# adc.net
KiCad netlist of a schematic drawn in EAGLE
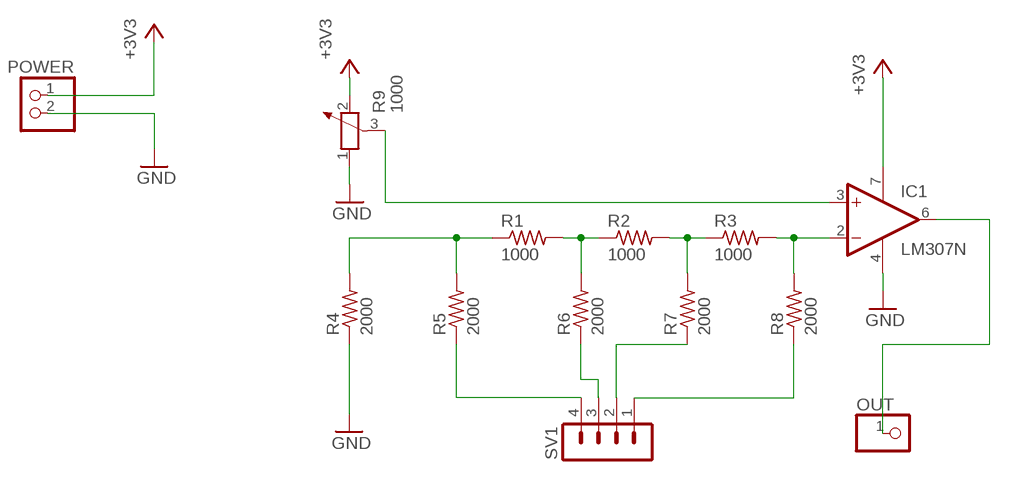
[diagram p0: schematic, sheet 1]

(export (version "E")
  (design (tool "Eeschema 10.0.6"))
  (components
    (comp (ref "IC1")
      (value "LM307N")
      (footprint "eagle-import:DIL08")
      (libsource (lib "eagle-import") (part "LM307N"))
    )
    (comp (ref "OUT")
      (value "PINHD-1X1")
      (footprint "eagle-import:1X01")
      (libsource (lib "eagle-import") (part "PINHD-1X1"))
    )
    (comp (ref "POWER")
      (value "PINHD-1X2")
      (footprint "eagle-import:1X02")
      (libsource (lib "eagle-import") (part "PINHD-1X2"))
    )
    (comp (ref "R1")
      (value "1000")
      (footprint "eagle-import:0204_7")
      (libsource (lib "eagle-import") (part "R-US_0204/7"))
    )
    (comp (ref "R2")
      (value "1000")
      (footprint "eagle-import:0204_7")
      (libsource (lib "eagle-import") (part "R-US_0204/7"))
    )
    (comp (ref "R3")
      (value "1000")
      (footprint "eagle-import:0204_7")
      (libsource (lib "eagle-import") (part "R-US_0204/7"))
    )
    (comp (ref "R4")
      (value "2000")
      (footprint "eagle-import:0204_7")
      (libsource (lib "eagle-import") (part "R-US_0204/7"))
    )
    (comp (ref "R5")
      (value "2000")
      (footprint "eagle-import:0204_7")
      (libsource (lib "eagle-import") (part "R-US_0204/7"))
    )
    (comp (ref "R6")
      (value "2000")
      (footprint "eagle-import:0204_7")
      (libsource (lib "eagle-import") (part "R-US_0204/7"))
    )
    (comp (ref "R7")
      (value "2000")
      (footprint "eagle-import:0204_7")
      (libsource (lib "eagle-import") (part "R-US_0204/7"))
    )
    (comp (ref "R8")
      (value "2000")
      (footprint "eagle-import:0204_7")
      (libsource (lib "eagle-import") (part "R-US_0204/7"))
    )
    (comp (ref "R9")
      (value "1000")
      (footprint "eagle-import:PT-10")
      (libsource (lib "eagle-import") (part "POTENTIOMETER_PT-10"))
    )
    (comp (ref "SV1")
      (value "MA04-1")
      (footprint "eagle-import:MA04-1")
      (libsource (lib "eagle-import") (part "MA04-1"))
    )
  )
  (nets
    (net (code "1") (name "+3V3") (class "Default")
      (node (ref "IC1") (pin "7") (pinfunction "V+_7") (pintype "power_in"))
      (node (ref "POWER") (pin "1") (pinfunction "1_1") (pintype "passive"))
      (node (ref "R9") (pin "2") (pinfunction "2_2") (pintype "passive"))
    )
    (net (code "2") (name "GND") (class "Default")
      (node (ref "IC1") (pin "4") (pinfunction "V-_4") (pintype "power_in"))
      (node (ref "POWER") (pin "2") (pinfunction "2_2") (pintype "passive"))
      (node (ref "R4") (pin "1") (pinfunction "1_1") (pintype "passive"))
      (node (ref "R9") (pin "1") (pinfunction "1_1") (pintype "passive"))
    )
    (net (code "3") (name "Net-(IC1-+IN)") (class "Default")
      (node (ref "IC1") (pin "3") (pinfunction "+IN_3") (pintype "input"))
      (node (ref "R9") (pin "3") (pinfunction "3_3") (pintype "passive"))
    )
    (net (code "4") (name "Net-(IC1--IN)") (class "Default")
      (node (ref "IC1") (pin "2") (pinfunction "-IN_2") (pintype "input"))
      (node (ref "R3") (pin "2") (pinfunction "2_2") (pintype "passive"))
      (node (ref "R8") (pin "2") (pinfunction "2_2") (pintype "passive"))
    )
    (net (code "5") (name "Net-(IC1-OUT)") (class "Default")
      (node (ref "IC1") (pin "6") (pinfunction "OUT_6") (pintype "output"))
      (node (ref "OUT") (pin "1") (pinfunction "1_1") (pintype "passive"))
    )
    (net (code "6") (name "Net-(R1-Pad1)") (class "Default")
      (node (ref "R1") (pin "1") (pinfunction "1_1") (pintype "passive"))
      (node (ref "R4") (pin "2") (pinfunction "2_2") (pintype "passive"))
      (node (ref "R5") (pin "2") (pinfunction "2_2") (pintype "passive"))
    )
    (net (code "7") (name "Net-(R1-Pad2)") (class "Default")
      (node (ref "R1") (pin "2") (pinfunction "2_2") (pintype "passive"))
      (node (ref "R2") (pin "1") (pinfunction "1_1") (pintype "passive"))
      (node (ref "R6") (pin "2") (pinfunction "2_2") (pintype "passive"))
    )
    (net (code "8") (name "Net-(R2-Pad2)") (class "Default")
      (node (ref "R2") (pin "2") (pinfunction "2_2") (pintype "passive"))
      (node (ref "R3") (pin "1") (pinfunction "1_1") (pintype "passive"))
      (node (ref "R7") (pin "2") (pinfunction "2_2") (pintype "passive"))
    )
    (net (code "9") (name "Net-(R5-Pad1)") (class "Default")
      (node (ref "R5") (pin "1") (pinfunction "1_1") (pintype "passive"))
      (node (ref "SV1") (pin "4") (pinfunction "4_4") (pintype "passive"))
    )
    (net (code "10") (name "Net-(R6-Pad1)") (class "Default")
      (node (ref "R6") (pin "1") (pinfunction "1_1") (pintype "passive"))
      (node (ref "SV1") (pin "3") (pinfunction "3_3") (pintype "passive"))
    )
    (net (code "11") (name "Net-(R7-Pad1)") (class "Default")
      (node (ref "R7") (pin "1") (pinfunction "1_1") (pintype "passive"))
      (node (ref "SV1") (pin "2") (pinfunction "2_2") (pintype "passive"))
    )
    (net (code "12") (name "Net-(R8-Pad1)") (class "Default")
      (node (ref "R8") (pin "1") (pinfunction "1_1") (pintype "passive"))
      (node (ref "SV1") (pin "1") (pinfunction "1_1") (pintype "passive"))
    )
  )
)
